# Adafruit_Feather_M0_Basic_rev_C.net
KiCad netlist of a schematic drawn in EAGLE
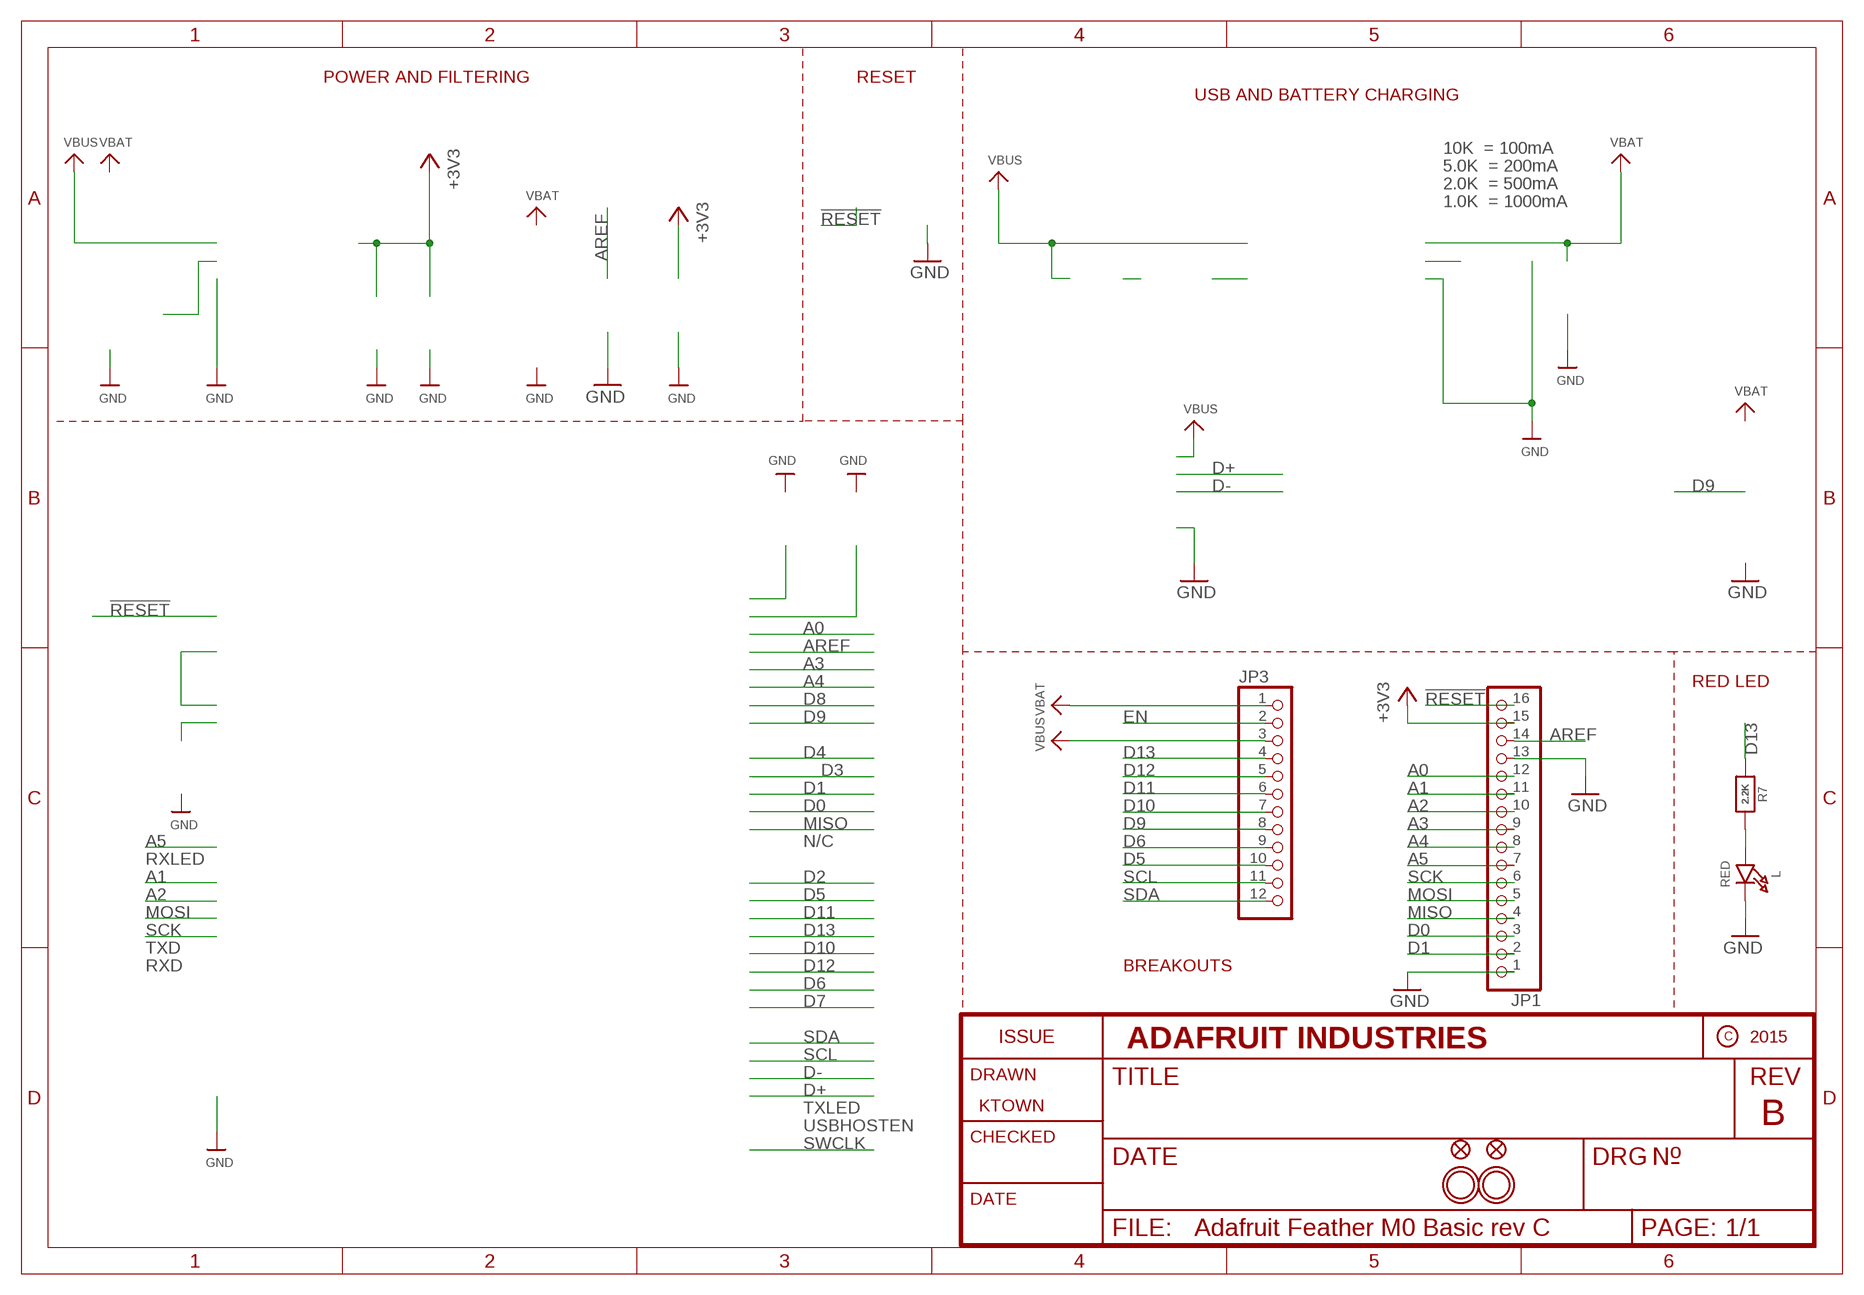
[diagram p0: schematic, sheet 1]

(export (version "E")
  (design (tool "Eeschema 10.0.6"))
  (components
    (comp (ref "JP1")
      (value "HEADER-1X16ROUND")
      (footprint "eagle-import:1X16_ROUND")
      (libsource (lib "eagle-import") (part "HEADER-1X16ROUND"))
    )
    (comp (ref "JP3")
      (value "HEADER-1X12")
      (footprint "eagle-import:1X12_ROUND")
      (libsource (lib "eagle-import") (part "HEADER-1X12"))
    )
    (comp (ref "L")
      (value "RED")
      (footprint "eagle-import:CHIPLED_0805_NOOUTLINE")
      (libsource (lib "eagle-import") (part "LED0805_NOOUTLINE"))
    )
    (comp (ref "R7")
      (value "2.2K")
      (footprint "eagle-import:0603-NO")
      (libsource (lib "eagle-import") (part "RESISTOR_0603_NOOUT"))
    )
    (comp (ref "U$31")
      (value "MOUNTINGHOLE2.5")
      (footprint "eagle-import:MOUNTINGHOLE_2.5_PLATED")
      (libsource (lib "eagle-import") (part "MOUNTINGHOLE2.5"))
    )
    (comp (ref "U$32")
      (value "MOUNTINGHOLE2.5")
      (footprint "eagle-import:MOUNTINGHOLE_2.5_PLATED")
      (libsource (lib "eagle-import") (part "MOUNTINGHOLE2.5"))
    )
    (comp (ref "U$34")
      (value "FIDUCIAL\"\"")
      (footprint "eagle-import:FIDUCIAL_1MM")
      (libsource (lib "eagle-import") (part "FIDUCIAL{dblquote}{dblquote}"))
    )
    (comp (ref "U$35")
      (value "FIDUCIAL\"\"")
      (footprint "eagle-import:FIDUCIAL_1MM")
      (libsource (lib "eagle-import") (part "FIDUCIAL{dblquote}{dblquote}"))
    )
  )
  (nets
    (net (code "1") (name "+3V3") (class "Default")
      (node (ref "JP1") (pin "15") (pinfunction "15_15") (pintype "passive"))
    )
    (net (code "2") (name "/A0") (class "Default")
      (node (ref "JP1") (pin "12") (pinfunction "12_12") (pintype "passive"))
    )
    (net (code "3") (name "/A1") (class "Default")
      (node (ref "JP1") (pin "11") (pinfunction "11_11") (pintype "passive"))
    )
    (net (code "4") (name "/A2") (class "Default")
      (node (ref "JP1") (pin "10") (pinfunction "10_10") (pintype "passive"))
    )
    (net (code "5") (name "/A3") (class "Default")
      (node (ref "JP1") (pin "9") (pinfunction "9_9") (pintype "passive"))
    )
    (net (code "6") (name "/A4") (class "Default")
      (node (ref "JP1") (pin "8") (pinfunction "8_8") (pintype "passive"))
    )
    (net (code "7") (name "/A5") (class "Default")
      (node (ref "JP1") (pin "7") (pinfunction "7_7") (pintype "passive"))
    )
    (net (code "8") (name "/AREF") (class "Default")
      (node (ref "JP1") (pin "14") (pinfunction "14_14") (pintype "passive"))
    )
    (net (code "11") (name "/D0") (class "Default")
      (node (ref "JP1") (pin "3") (pinfunction "3_3") (pintype "passive"))
    )
    (net (code "12") (name "/D1") (class "Default")
      (node (ref "JP1") (pin "2") (pinfunction "2_2") (pintype "passive"))
    )
    (net (code "16") (name "/D5") (class "Default")
      (node (ref "JP3") (pin "10") (pinfunction "10_10") (pintype "passive"))
    )
    (net (code "17") (name "/D6") (class "Default")
      (node (ref "JP3") (pin "9") (pinfunction "9_9") (pintype "passive"))
    )
    (net (code "20") (name "/D9") (class "Default")
      (node (ref "JP3") (pin "8") (pinfunction "8_8") (pintype "passive"))
    )
    (net (code "21") (name "/D10") (class "Default")
      (node (ref "JP3") (pin "7") (pinfunction "7_7") (pintype "passive"))
    )
    (net (code "22") (name "/D11") (class "Default")
      (node (ref "JP3") (pin "6") (pinfunction "6_6") (pintype "passive"))
    )
    (net (code "23") (name "/D12") (class "Default")
      (node (ref "JP3") (pin "5") (pinfunction "5_5") (pintype "passive"))
    )
    (net (code "24") (name "/D13") (class "Default")
      (node (ref "JP3") (pin "4") (pinfunction "4_4") (pintype "passive"))
      (node (ref "R7") (pin "1") (pinfunction "1_1") (pintype "passive"))
    )
    (net (code "25") (name "/EN") (class "Default")
      (node (ref "JP3") (pin "2") (pinfunction "2_2") (pintype "passive"))
    )
    (net (code "26") (name "/MISO") (class "Default")
      (node (ref "JP1") (pin "4") (pinfunction "4_4") (pintype "passive"))
    )
    (net (code "27") (name "/MOSI") (class "Default")
      (node (ref "JP1") (pin "5") (pinfunction "5_5") (pintype "passive"))
    )
    (net (code "28") (name "/SCK") (class "Default")
      (node (ref "JP1") (pin "6") (pinfunction "6_6") (pintype "passive"))
    )
    (net (code "29") (name "/SCL") (class "Default")
      (node (ref "JP3") (pin "11") (pinfunction "11_11") (pintype "passive"))
    )
    (net (code "30") (name "/SDA") (class "Default")
      (node (ref "JP3") (pin "12") (pinfunction "12_12") (pintype "passive"))
    )
    (net (code "32") (name "/~{RESET}") (class "Default")
      (node (ref "JP1") (pin "16") (pinfunction "16_16") (pintype "passive"))
    )
    (net (code "33") (name "GND") (class "Default")
      (node (ref "JP1") (pin "1") (pinfunction "1_1") (pintype "passive"))
      (node (ref "JP1") (pin "13") (pinfunction "13_13") (pintype "passive"))
      (node (ref "L") (pin "C") (pinfunction "C_C") (pintype "passive"))
    )
    (net (code "34") (name "Net-(L-PadA)") (class "Default")
      (node (ref "L") (pin "A") (pinfunction "A_A") (pintype "passive"))
      (node (ref "R7") (pin "2") (pinfunction "2_2") (pintype "passive"))
    )
    (net (code "35") (name "VBAT") (class "Default")
      (node (ref "JP3") (pin "1") (pinfunction "1_1") (pintype "passive"))
    )
    (net (code "36") (name "VBUS") (class "Default")
      (node (ref "JP3") (pin "3") (pinfunction "3_3") (pintype "passive"))
    )
  )
)
